# GateDriver.net
KiCad netlist of a schematic drawn in Altium Designer
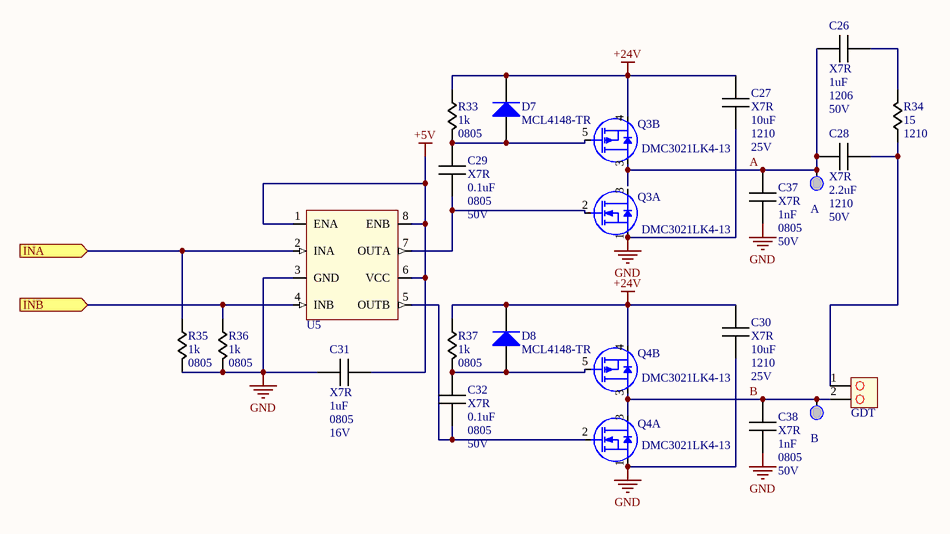
[diagram p0: GateDriver.SchDoc]

(export (version "E")
  (design (tool "Eeschema 10.0.6"))
  (components
    (comp (ref "A")
      (value "Testpoint")
      (footprint "Keystone5002")
      (fields (field (name "DIGIKEY PART") "36-5002-ND") (field (name "MOUSER PART") "534-5002"))
      (libsource (lib "UD2 CPLD") (part "Testpoint"))
    )
    (comp (ref "B")
      (value "Testpoint")
      (footprint "Keystone5002")
      (fields (field (name "DIGIKEY PART") "36-5002-ND") (field (name "MOUSER PART") "534-5002"))
      (libsource (lib "UD2 CPLD") (part "Testpoint"))
    )
    (comp (ref "C26")
      (value "GRM31MR71H105KA88L")
      (footprint "1206C")
      (description "CAP CER 1UF 50V X7R 1206")
      (fields
        (field (name "TOLERANCE") "10%")
        (field (name "MATERIAL") "X7R")
        (field (name "CAPACITANCE") "1uF")
        (field (name "PACKAGE") "1206")
        (field (name "VOLTAGE") "50V")
        (field (name "MOUSER PART") "81-GRM31MR71H105KA88")
      )
      (libsource (lib "UD2 CPLD") (part "Capacitor"))
    )
    (comp (ref "C27")
      (value "885012209028")
      (footprint "1210C")
      (description "CAP CER 10UF 25V X7R 1210")
      (fields
        (field (name "MATERIAL") "X7R")
        (field (name "CAPACITANCE") "10uF")
        (field (name "PACKAGE") "1210")
        (field (name "VOLTAGE") "25V")
        (field (name "MOUSER PART") "710-885012207094")
        (field (name "DIGIKEY PART") "732-7729-1-ND")
      )
      (libsource (lib "UD2 CPLD") (part "Capacitor"))
    )
    (comp (ref "C28")
      (value "CGA6M3X7R1H225K200AB")
      (footprint "1210C")
      (description "CAP ALUM 100UF 20% 16V RADIAL")
      (fields
        (field (name "TOLERANCE") "10%")
        (field (name "MATERIAL") "X7R")
        (field (name "CAPACITANCE") "2.2uF")
        (field (name "PACKAGE") "1210")
        (field (name "VOLTAGE") "50V")
        (field (name "MOUSER PART") "810-CGA6M3X7R1H225K")
      )
      (libsource (lib "UD2 CPLD") (part "Capacitor"))
    )
    (comp (ref "C29")
      (value "08055C104JAT2A")
      (footprint "0805C")
      (description "CAP CER 0.1UF 50V X7R 0805")
      (fields
        (field (name "MATERIAL") "X7R")
        (field (name "CAPACITANCE") "0.1uF")
        (field (name "PACKAGE") "0805")
        (field (name "VOLTAGE") "50V")
        (field (name "MOUSER PART") "581-08055C104J")
        (field (name "DIGIKEY PART") "478-3352-1-ND")
      )
      (libsource (lib "UD2 CPLD") (part "Capacitor"))
    )
    (comp (ref "C30")
      (value "885012209028")
      (footprint "1210C")
      (description "CAP CER 10UF 25V X7R 1210")
      (fields
        (field (name "MATERIAL") "X7R")
        (field (name "CAPACITANCE") "10uF")
        (field (name "PACKAGE") "1210")
        (field (name "VOLTAGE") "25V")
        (field (name "MOUSER PART") "710-885012207094")
        (field (name "DIGIKEY PART") "732-7729-1-ND")
      )
      (libsource (lib "UD2 CPLD") (part "Capacitor"))
    )
    (comp (ref "C31")
      (value "CC0805KKX7R7BB105")
      (footprint "0805C")
      (description "CAP CER 1UF 16V X7R 0805")
      (fields
        (field (name "TOLERANCE") "10%")
        (field (name "MATERIAL") "X7R")
        (field (name "CAPACITANCE") "1uF")
        (field (name "PACKAGE") "0805")
        (field (name "VOLTAGE") "16V")
        (field (name "MOUSER PART") "603-CC805KKX7R7BB105")
      )
      (libsource (lib "UD2 CPLD") (part "Capacitor"))
    )
    (comp (ref "C32")
      (value "08055C104JAT2A")
      (footprint "0805C")
      (description "CAP CER 0.1UF 50V X7R 0805")
      (fields
        (field (name "MATERIAL") "X7R")
        (field (name "CAPACITANCE") "0.1uF")
        (field (name "PACKAGE") "0805")
        (field (name "VOLTAGE") "50V")
        (field (name "MOUSER PART") "581-08055C104J")
        (field (name "DIGIKEY PART") "478-3352-1-ND")
      )
      (libsource (lib "UD2 CPLD") (part "Capacitor"))
    )
    (comp (ref "C37")
      (value "C0805C102K5RACTU")
      (footprint "0805C")
      (description "CAP CER 1000PF 50V X7R 0805")
      (fields
        (field (name "MATERIAL") "X7R")
        (field (name "CAPACITANCE") "1nF")
        (field (name "PACKAGE") "0805")
        (field (name "VOLTAGE") "50V")
        (field (name "MOUSER PART") "80-C0805C102K5R")
        (field (name "DIGIKEY PART") "399-1147-1-ND")
      )
      (libsource (lib "UD2 CPLD") (part "Capacitor"))
    )
    (comp (ref "C38")
      (value "C0805C102K5RACTU")
      (footprint "0805C")
      (description "CAP CER 1000PF 50V X7R 0805")
      (fields
        (field (name "MATERIAL") "X7R")
        (field (name "CAPACITANCE") "1nF")
        (field (name "PACKAGE") "0805")
        (field (name "VOLTAGE") "50V")
        (field (name "MOUSER PART") "80-C0805C102K5R")
        (field (name "DIGIKEY PART") "399-1147-1-ND")
      )
      (libsource (lib "UD2 CPLD") (part "Capacitor"))
    )
    (comp (ref "D7")
      (value "MCL4148-TR")
      (footprint "MicroMELF")
      (description "DIODE GEN 75V 150MA MICROMELF")
      (fields (field (name "MOUSER PART") "78-MCL4148") (field (name "DIGIKEY PART") "MCL4148CT-ND"))
      (libsource (lib "UD2 CPLD") (part "1N4148"))
    )
    (comp (ref "D8")
      (value "MCL4148-TR")
      (footprint "MicroMELF")
      (description "DIODE GEN 75V 150MA MICROMELF")
      (fields (field (name "MOUSER PART") "78-MCL4148") (field (name "DIGIKEY PART") "MCL4148CT-ND"))
      (libsource (lib "UD2 CPLD") (part "1N4148"))
    )
    (comp (ref "GDT")
      (value "22-23-2021")
      (footprint "22-23-2021")
      (description "CONN HEADER 2POS .100 VERT TIN")
      (fields (field (name "MOUSER PART") "538-22-23-2021") (field (name "DIGIKEY PART") "WM4200-ND"))
      (libsource (lib "UD2 CPLD") (part "22-23-2021"))
    )
    (comp (ref "Q3")
      (value "DMC3021LK4-13")
      (footprint "TO-252")
      (description "MOSFET N/P-CH 30V TO252-4L")
      (fields (field (name "MOUSER PART") "512-FDD8424H") (field (name "DIGIKEY PART") "FDD8424HCT-ND"))
      (libsource (lib "UD2 CPLD") (part "FDD8424H"))
    )
    (comp (ref "Q4")
      (value "DMC3021LK4-13")
      (footprint "TO-252")
      (description "MOSFET N/P-CH 30V TO252-4L")
      (fields (field (name "MOUSER PART") "512-FDD8424H") (field (name "DIGIKEY PART") "FDD8424HCT-ND"))
      (libsource (lib "UD2 CPLD") (part "FDD8424H"))
    )
    (comp (ref "R33")
      (value "RC0805FR-071KL")
      (footprint "0805R")
      (description "RES SMD 1K OHM 1% 1/8W 0805")
      (fields
        (field (name "POWER") "0.125W")
        (field (name "RESISTANCE") "1k")
        (field (name "PACKAGE") "0805")
        (field (name "TOLERANCE") "1%")
      )
      (libsource (lib "UD2 CPLD") (part "Resistor"))
    )
    (comp (ref "R34")
      (value "CRCW121015R0JNEAHP")
      (footprint "1210R")
      (description "RES SMD 15 OHM 5% 3/4W 1210")
      (fields
        (field (name "RESISTANCE") "15")
        (field (name "PACKAGE") "1210")
        (field (name "POWER") "750mW")
        (field (name "TOLERANCE") "5%")
      )
      (libsource (lib "UD2 CPLD") (part "Resistor"))
    )
    (comp (ref "R35")
      (value "RC0805FR-071KL")
      (footprint "0805R")
      (description "RES SMD 1K OHM 1% 1/8W 0805")
      (fields
        (field (name "POWER") "0.125W")
        (field (name "RESISTANCE") "1k")
        (field (name "PACKAGE") "0805")
        (field (name "TOLERANCE") "1%")
      )
      (libsource (lib "UD2 CPLD") (part "Resistor"))
    )
    (comp (ref "R36")
      (value "RC0805FR-071KL")
      (footprint "0805R")
      (description "RES SMD 1K OHM 1% 1/8W 0805")
      (fields
        (field (name "POWER") "0.125W")
        (field (name "RESISTANCE") "1k")
        (field (name "PACKAGE") "0805")
        (field (name "TOLERANCE") "1%")
      )
      (libsource (lib "UD2 CPLD") (part "Resistor"))
    )
    (comp (ref "R37")
      (value "RC0805FR-071KL")
      (footprint "0805R")
      (description "RES SMD 1K OHM 1% 1/8W 0805")
      (fields
        (field (name "POWER") "0.125W")
        (field (name "RESISTANCE") "1k")
        (field (name "PACKAGE") "0805")
        (field (name "TOLERANCE") "1%")
      )
      (libsource (lib "UD2 CPLD") (part "Resistor"))
    )
    (comp (ref "U5")
      (value "UCC27423DR")
      (footprint "SOIC-8")
      (description "IC DRIVER MOSFET 1.5A DUAL 8SOIC")
      (fields (field (name "MOUSER PART") "595-UCC27423DR") (field (name "DIGIKEY PART") "296-41798-1-ND"))
      (libsource (lib "UD2 CPLD") (part "UCC27423D"))
    )
  )
  (nets
    (net (code "1") (name "+5V") (class "Default")
      (node (ref "C31") (pin "2") (pinfunction "2_2") (pintype "passive"))
      (node (ref "U5") (pin "1") (pinfunction "ENA_1") (pintype "power_in"))
      (node (ref "U5") (pin "6") (pinfunction "VCC_6") (pintype "passive"))
      (node (ref "U5") (pin "8") (pinfunction "ENB_8") (pintype "passive"))
    )
    (net (code "2") (name "+24V") (class "Default")
      (node (ref "C27") (pin "1") (pinfunction "1_1") (pintype "passive"))
      (node (ref "C30") (pin "1") (pinfunction "1_1") (pintype "passive"))
      (node (ref "D7") (pin "K") (pinfunction "K_K") (pintype "passive"))
      (node (ref "D8") (pin "K") (pinfunction "K_K") (pintype "passive"))
      (node (ref "Q3") (pin "4") (pinfunction "S2_4") (pintype "passive"))
      (node (ref "Q4") (pin "4") (pinfunction "S2_4") (pintype "passive"))
      (node (ref "R33") (pin "2") (pinfunction "2_2") (pintype "passive"))
      (node (ref "R37") (pin "2") (pinfunction "2_2") (pintype "passive"))
    )
    (net (code "3") (name "/A") (class "Default")
      (node (ref "A") (pin "1") (pinfunction "1_1") (pintype "passive"))
      (node (ref "C26") (pin "1") (pinfunction "1_1") (pintype "passive"))
      (node (ref "C28") (pin "1") (pinfunction "1_1") (pintype "passive"))
      (node (ref "C37") (pin "2") (pinfunction "2_2") (pintype "passive"))
      (node (ref "Q3") (pin "3") (pinfunction "D1/D2_3") (pintype "passive"))
    )
    (net (code "4") (name "/B") (class "Default")
      (node (ref "B") (pin "1") (pinfunction "1_1") (pintype "passive"))
      (node (ref "C38") (pin "2") (pinfunction "2_2") (pintype "passive"))
      (node (ref "GDT") (pin "2") (pinfunction "2_2") (pintype "passive"))
      (node (ref "Q4") (pin "3") (pinfunction "D1/D2_3") (pintype "passive"))
    )
    (net (code "5") (name "/INA") (class "Default")
      (node (ref "R35") (pin "2") (pinfunction "2_2") (pintype "passive"))
      (node (ref "U5") (pin "2") (pinfunction "INA_2") (pintype "input"))
    )
    (net (code "6") (name "/INB") (class "Default")
      (node (ref "R36") (pin "2") (pinfunction "2_2") (pintype "passive"))
      (node (ref "U5") (pin "4") (pinfunction "INB_4") (pintype "input"))
    )
    (net (code "7") (name "GND") (class "Default")
      (node (ref "C27") (pin "2") (pinfunction "2_2") (pintype "passive"))
      (node (ref "C30") (pin "2") (pinfunction "2_2") (pintype "passive"))
      (node (ref "C31") (pin "1") (pinfunction "1_1") (pintype "passive"))
      (node (ref "C37") (pin "1") (pinfunction "1_1") (pintype "passive"))
      (node (ref "C38") (pin "1") (pinfunction "1_1") (pintype "passive"))
      (node (ref "Q3") (pin "1") (pinfunction "S1_1") (pintype "passive"))
      (node (ref "Q4") (pin "1") (pinfunction "S1_1") (pintype "passive"))
      (node (ref "R35") (pin "1") (pinfunction "1_1") (pintype "passive"))
      (node (ref "R36") (pin "1") (pinfunction "1_1") (pintype "passive"))
      (node (ref "U5") (pin "3") (pinfunction "GND_3") (pintype "passive"))
    )
    (net (code "8") (name "Net-(C26-Pad2)") (class "Default")
      (node (ref "C26") (pin "2") (pinfunction "2_2") (pintype "passive"))
      (node (ref "R34") (pin "1") (pinfunction "1_1") (pintype "passive"))
    )
    (net (code "9") (name "Net-(C28-Pad2)") (class "Default")
      (node (ref "C28") (pin "2") (pinfunction "2_2") (pintype "passive"))
      (node (ref "GDT") (pin "1") (pinfunction "1_1") (pintype "passive"))
      (node (ref "R34") (pin "2") (pinfunction "2_2") (pintype "passive"))
    )
    (net (code "10") (name "Net-(Q3A-G1)") (class "Default")
      (node (ref "C29") (pin "1") (pinfunction "1_1") (pintype "passive"))
      (node (ref "Q3") (pin "2") (pinfunction "G1_2") (pintype "passive"))
      (node (ref "U5") (pin "7") (pinfunction "OUTA_7") (pintype "output"))
    )
    (net (code "11") (name "Net-(Q3B-G2)") (class "Default")
      (node (ref "C29") (pin "2") (pinfunction "2_2") (pintype "passive"))
      (node (ref "D7") (pin "A") (pinfunction "A_A") (pintype "passive"))
      (node (ref "Q3") (pin "5") (pinfunction "G2_5") (pintype "passive"))
      (node (ref "R33") (pin "1") (pinfunction "1_1") (pintype "passive"))
    )
    (net (code "12") (name "Net-(Q4A-G1)") (class "Default")
      (node (ref "C32") (pin "1") (pinfunction "1_1") (pintype "passive"))
      (node (ref "Q4") (pin "2") (pinfunction "G1_2") (pintype "passive"))
      (node (ref "U5") (pin "5") (pinfunction "OUTB_5") (pintype "output"))
    )
    (net (code "13") (name "Net-(Q4B-G2)") (class "Default")
      (node (ref "C32") (pin "2") (pinfunction "2_2") (pintype "passive"))
      (node (ref "D8") (pin "A") (pinfunction "A_A") (pintype "passive"))
      (node (ref "Q4") (pin "5") (pinfunction "G2_5") (pintype "passive"))
      (node (ref "R37") (pin "1") (pinfunction "1_1") (pintype "passive"))
    )
    (net (code "14") (name "unconnected-(Q3A-D1{slash}D2-Pad3)") (class "Default")
      (node (ref "Q3") (pin "3") (pinfunction "D1/D2_3") (pintype "passive"))
    )
  )
)
